# Group12_411_REV1.net
KiCad netlist of a schematic drawn in EAGLE
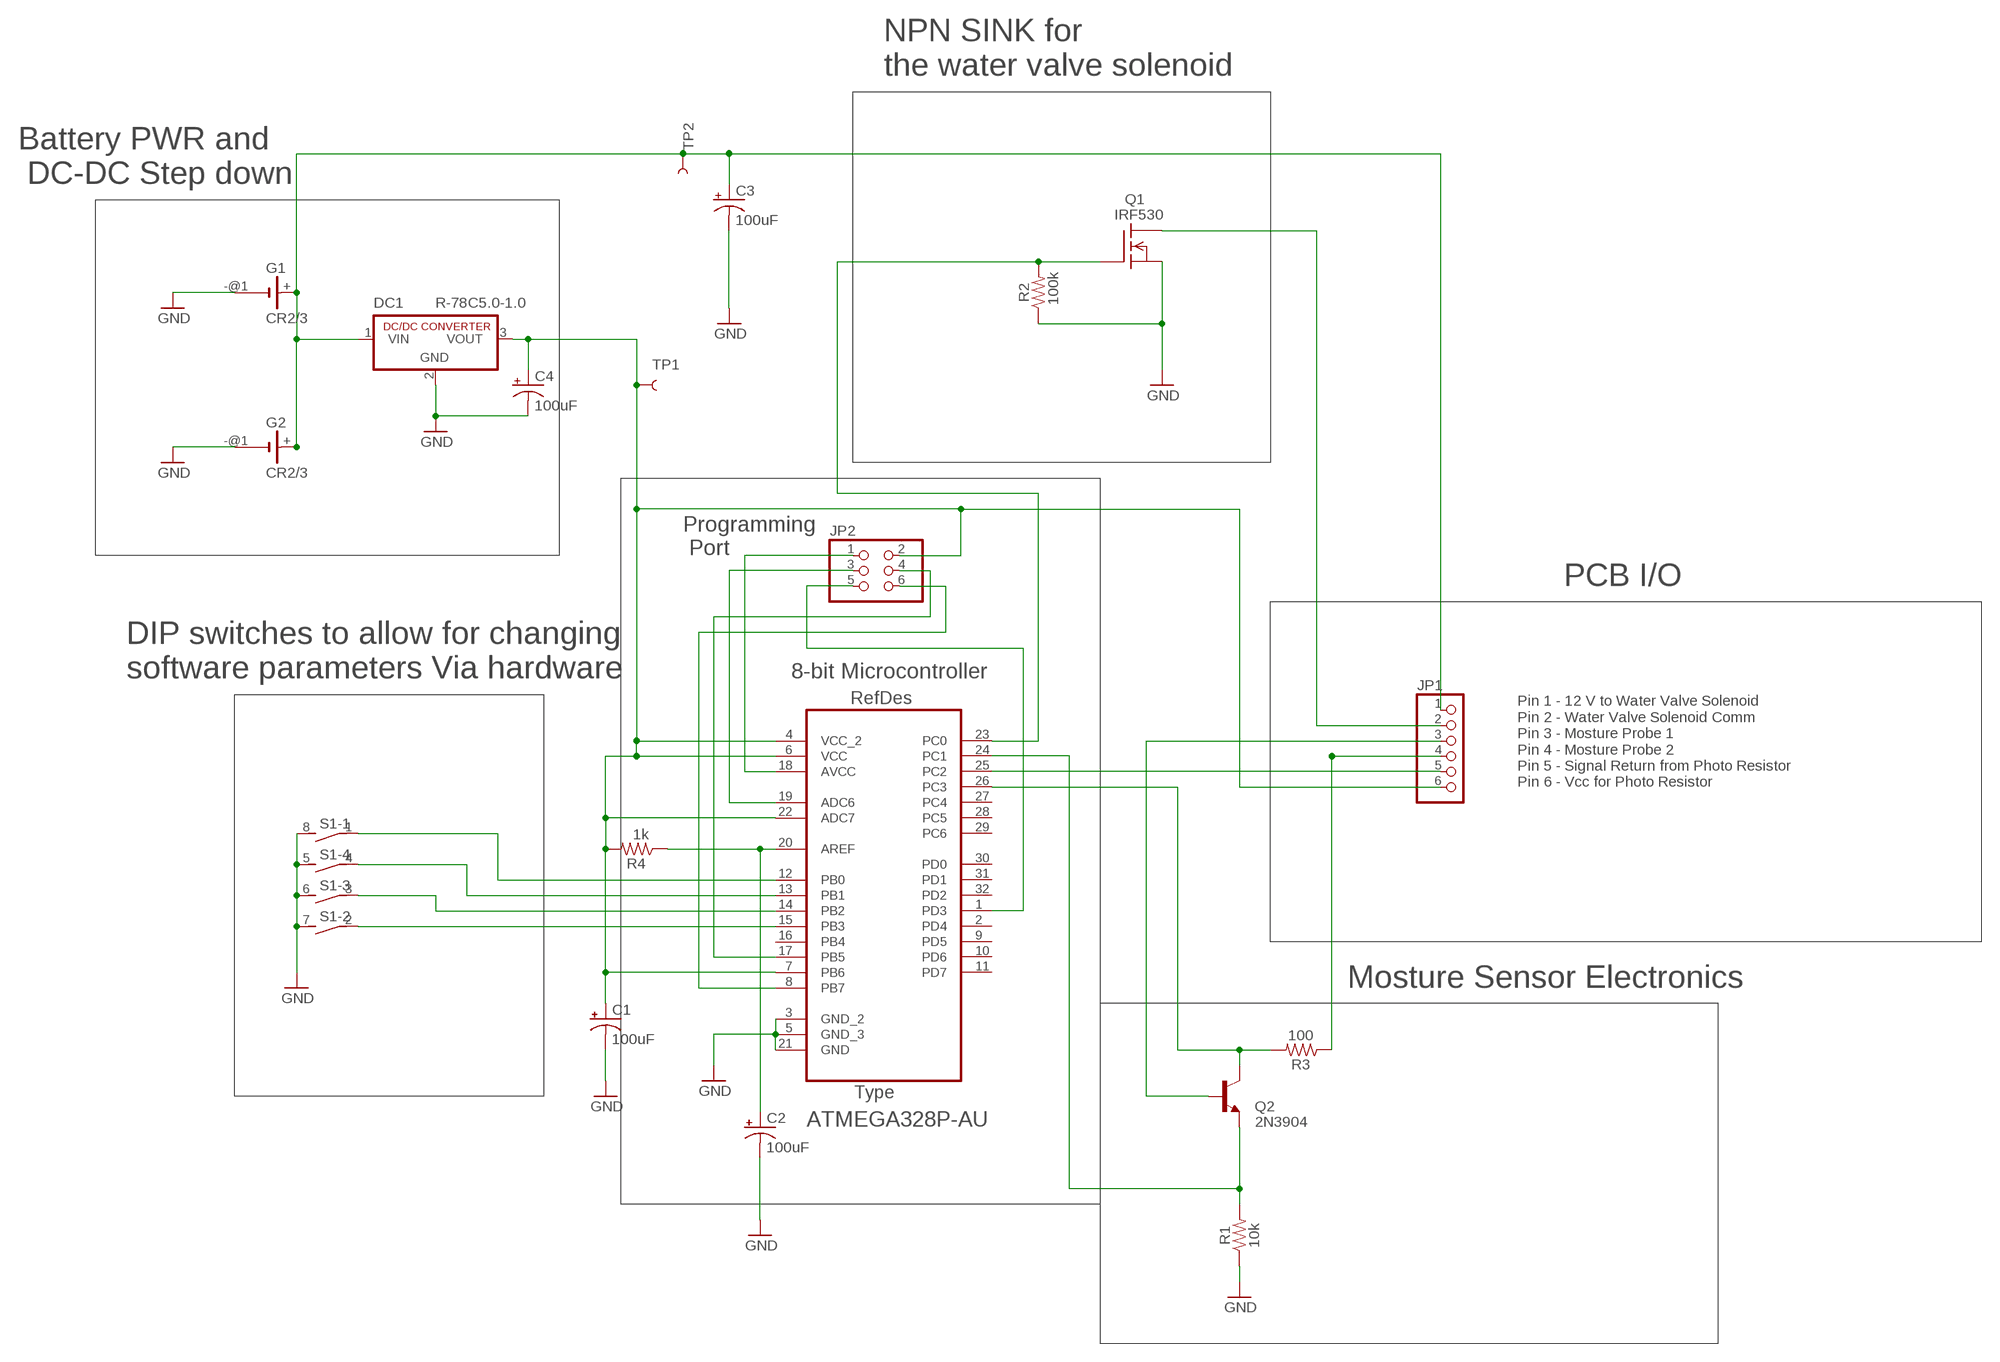
[diagram p0: schematic, sheet 1]

(export (version "E")
  (design (tool "Eeschema 10.0.6"))
  (components
    (comp (ref "ATMEGA328")
      (value "ATMEGA328P-AU")
      (footprint "eagle-import:QFP80P900X900X120-32N")
      (description "8-bit Microcontroller")
      (fields (field (name "MPN") "ATMEGA328P-AU"))
      (libsource (lib "eagle-import") (part "ATMEGA328P-AU"))
    )
    (comp (ref "C1")
      (value "100uF")
      (footprint "eagle-import:EIA7343")
      (libsource (lib "eagle-import") (part "100UF-POLAR-EIA7343-16V-10%(TANT)"))
    )
    (comp (ref "C2")
      (value "100uF")
      (footprint "eagle-import:EIA7343")
      (libsource (lib "eagle-import") (part "100UF-POLAR-EIA7343-16V-10%(TANT)"))
    )
    (comp (ref "C3")
      (value "100uF")
      (footprint "eagle-import:EIA7343")
      (libsource (lib "eagle-import") (part "100UF-POLAR-EIA7343-16V-10%(TANT)"))
    )
    (comp (ref "C4")
      (value "100uF")
      (footprint "eagle-import:EIA7343")
      (libsource (lib "eagle-import") (part "100UF-POLAR-EIA7343-16V-10%(TANT)"))
    )
    (comp (ref "DC1")
      (value "R-78C5.0-1.0")
      (footprint "eagle-import:SIP3")
      (libsource (lib "eagle-import") (part "R-78C-1.05.0"))
    )
    (comp (ref "G1")
      (value "CR2/3")
      (footprint "eagle-import:CR2_3")
      (libsource (lib "eagle-import") (part "CR2/3"))
    )
    (comp (ref "G2")
      (value "CR2/3")
      (footprint "eagle-import:CR2_3")
      (libsource (lib "eagle-import") (part "CR2/3"))
    )
    (comp (ref "JP1")
      (value "PINHD-1X6")
      (footprint "eagle-import:1X06")
      (libsource (lib "eagle-import") (part "PINHD-1X6"))
    )
    (comp (ref "JP2")
      (value "PINHD-2X3")
      (footprint "eagle-import:2X03")
      (libsource (lib "eagle-import") (part "PINHD-2X3"))
    )
    (comp (ref "Q1")
      (value "VN66AF")
      (footprint "eagle-import:TO202")
      (libsource (lib "eagle-import") (part "VN66AF"))
    )
    (comp (ref "Q2")
      (value "600mA/40V")
      (footprint "eagle-import:SOT23-3")
      (fields (field (name "Q") "2N3904"))
      (libsource (lib "eagle-import") (part "TRANS_NPN-MMBT2222AL"))
    )
    (comp (ref "R1")
      (value "R-US_M0805")
      (footprint "eagle-import:M0805")
      (fields (field (name "R") "10k"))
      (libsource (lib "eagle-import") (part "R-US_M0805"))
    )
    (comp (ref "R2")
      (value "R-US_M0805")
      (footprint "eagle-import:M0805")
      (fields (field (name "R") "100k"))
      (libsource (lib "eagle-import") (part "R-US_M0805"))
    )
    (comp (ref "R3")
      (value "R-US_M0805")
      (footprint "eagle-import:M0805")
      (fields (field (name "R") "100"))
      (libsource (lib "eagle-import") (part "R-US_M0805"))
    )
    (comp (ref "R4")
      (value "R-US_M0805")
      (footprint "eagle-import:M0805")
      (fields (field (name "R") "1k"))
      (libsource (lib "eagle-import") (part "R-US_M0805"))
    )
    (comp (ref "S1")
      (value "DIP04S")
      (footprint "eagle-import:DIP04S")
      (libsource (lib "eagle-import") (part "DIP04S"))
    )
    (comp (ref "TP1")
      (value "TEST-POINT3")
      (footprint "eagle-import:PAD.03X.03")
      (libsource (lib "eagle-import") (part "TEST-POINT3"))
    )
    (comp (ref "TP2")
      (value "TEST-POINT3")
      (footprint "eagle-import:PAD.03X.03")
      (libsource (lib "eagle-import") (part "TEST-POINT3"))
    )
  )
  (nets
    (net (code "1") (name "GND") (class "Default")
      (node (ref "ATMEGA328") (pin "21") (pinfunction "GND_21") (pintype "passive"))
      (node (ref "ATMEGA328") (pin "3") (pinfunction "GND_2_3") (pintype "passive"))
      (node (ref "ATMEGA328") (pin "5") (pinfunction "GND_3_5") (pintype "passive"))
      (node (ref "C1") (pin "C") (pinfunction "-_C") (pintype "passive"))
      (node (ref "C2") (pin "C") (pinfunction "-_C") (pintype "passive"))
      (node (ref "C3") (pin "C") (pinfunction "-_C") (pintype "passive"))
      (node (ref "C4") (pin "C") (pinfunction "-_C") (pintype "passive"))
      (node (ref "DC1") (pin "2") (pinfunction "GND_2") (pintype "passive"))
      (node (ref "G1") (pin "-@1") (pinfunction "-_-@1") (pintype "passive"))
      (node (ref "G2") (pin "-@1") (pinfunction "-_-@1") (pintype "passive"))
      (node (ref "Q1") (pin "1") (pinfunction "S_1") (pintype "passive"))
      (node (ref "R1") (pin "1") (pinfunction "1_1") (pintype "passive"))
      (node (ref "R2") (pin "1") (pinfunction "1_1") (pintype "passive"))
      (node (ref "S1") (pin "5") (pinfunction "2_5") (pintype "passive"))
      (node (ref "S1") (pin "6") (pinfunction "2_6") (pintype "passive"))
      (node (ref "S1") (pin "7") (pinfunction "2_7") (pintype "passive"))
      (node (ref "S1") (pin "8") (pinfunction "2_8") (pintype "passive"))
    )
    (net (code "2") (name "Net-(ATMEGA328-ADC6)") (class "Default")
      (node (ref "ATMEGA328") (pin "19") (pinfunction "ADC6_19") (pintype "input"))
      (node (ref "JP2") (pin "3") (pinfunction "3_3") (pintype "passive"))
    )
    (net (code "3") (name "Net-(ATMEGA328-ADC7)") (class "Default")
      (node (ref "ATMEGA328") (pin "22") (pinfunction "ADC7_22") (pintype "input"))
      (node (ref "ATMEGA328") (pin "4") (pinfunction "VCC_2_4") (pintype "power_in"))
      (node (ref "ATMEGA328") (pin "6") (pinfunction "VCC_6") (pintype "power_in"))
      (node (ref "ATMEGA328") (pin "7") (pinfunction "PB6_7") (pintype "bidirectional"))
      (node (ref "C1") (pin "A") (pinfunction "+_A") (pintype "passive"))
      (node (ref "C4") (pin "A") (pinfunction "+_A") (pintype "passive"))
      (node (ref "DC1") (pin "3") (pinfunction "VOUT_3") (pintype "passive"))
      (node (ref "JP1") (pin "6") (pinfunction "6_6") (pintype "passive"))
      (node (ref "JP2") (pin "2") (pinfunction "2_2") (pintype "passive"))
      (node (ref "R4") (pin "2") (pinfunction "2_2") (pintype "passive"))
      (node (ref "TP1") (pin "P$1") (pinfunction "1_P$1") (pintype "bidirectional"))
    )
    (net (code "4") (name "Net-(ATMEGA328-AREF)") (class "Default")
      (node (ref "ATMEGA328") (pin "20") (pinfunction "AREF_20") (pintype "input"))
      (node (ref "C2") (pin "A") (pinfunction "+_A") (pintype "passive"))
      (node (ref "R4") (pin "1") (pinfunction "1_1") (pintype "passive"))
    )
    (net (code "5") (name "Net-(ATMEGA328-AVCC)") (class "Default")
      (node (ref "ATMEGA328") (pin "18") (pinfunction "AVCC_18") (pintype "power_in"))
      (node (ref "JP2") (pin "1") (pinfunction "1_1") (pintype "passive"))
    )
    (net (code "6") (name "Net-(ATMEGA328-PB0)") (class "Default")
      (node (ref "ATMEGA328") (pin "12") (pinfunction "PB0_12") (pintype "bidirectional"))
      (node (ref "S1") (pin "1") (pinfunction "1_1") (pintype "passive"))
    )
    (net (code "7") (name "Net-(ATMEGA328-PB1)") (class "Default")
      (node (ref "ATMEGA328") (pin "13") (pinfunction "PB1_13") (pintype "bidirectional"))
      (node (ref "S1") (pin "4") (pinfunction "1_4") (pintype "passive"))
    )
    (net (code "8") (name "Net-(ATMEGA328-PB2)") (class "Default")
      (node (ref "ATMEGA328") (pin "14") (pinfunction "PB2_14") (pintype "bidirectional"))
      (node (ref "S1") (pin "3") (pinfunction "1_3") (pintype "passive"))
    )
    (net (code "9") (name "Net-(ATMEGA328-PB3)") (class "Default")
      (node (ref "ATMEGA328") (pin "15") (pinfunction "PB3_15") (pintype "bidirectional"))
      (node (ref "S1") (pin "2") (pinfunction "1_2") (pintype "passive"))
    )
    (net (code "10") (name "Net-(ATMEGA328-PB5)") (class "Default")
      (node (ref "ATMEGA328") (pin "17") (pinfunction "PB5_17") (pintype "bidirectional"))
      (node (ref "JP2") (pin "4") (pinfunction "4_4") (pintype "passive"))
    )
    (net (code "11") (name "Net-(ATMEGA328-PB7)") (class "Default")
      (node (ref "ATMEGA328") (pin "8") (pinfunction "PB7_8") (pintype "bidirectional"))
      (node (ref "JP2") (pin "6") (pinfunction "6_6") (pintype "passive"))
    )
    (net (code "12") (name "Net-(ATMEGA328-PC0)") (class "Default")
      (node (ref "ATMEGA328") (pin "23") (pinfunction "PC0_23") (pintype "bidirectional"))
      (node (ref "Q1") (pin "2") (pinfunction "G_2") (pintype "passive"))
      (node (ref "R2") (pin "2") (pinfunction "2_2") (pintype "passive"))
    )
    (net (code "13") (name "Net-(ATMEGA328-PC1)") (class "Default")
      (node (ref "ATMEGA328") (pin "24") (pinfunction "PC1_24") (pintype "bidirectional"))
      (node (ref "Q2") (pin "2") (pinfunction "E_2") (pintype "passive"))
      (node (ref "R1") (pin "2") (pinfunction "2_2") (pintype "passive"))
    )
    (net (code "14") (name "Net-(ATMEGA328-PC2)") (class "Default")
      (node (ref "ATMEGA328") (pin "25") (pinfunction "PC2_25") (pintype "bidirectional"))
      (node (ref "JP1") (pin "5") (pinfunction "5_5") (pintype "passive"))
    )
    (net (code "15") (name "Net-(ATMEGA328-PC3)") (class "Default")
      (node (ref "ATMEGA328") (pin "26") (pinfunction "PC3_26") (pintype "bidirectional"))
      (node (ref "Q2") (pin "3") (pinfunction "C_3") (pintype "passive"))
      (node (ref "R3") (pin "2") (pinfunction "2_2") (pintype "passive"))
    )
    (net (code "16") (name "Net-(ATMEGA328-PD3)") (class "Default")
      (node (ref "ATMEGA328") (pin "1") (pinfunction "PD3_1") (pintype "bidirectional"))
      (node (ref "JP2") (pin "5") (pinfunction "5_5") (pintype "passive"))
    )
    (net (code "17") (name "Net-(C3-+)") (class "Default")
      (node (ref "C3") (pin "A") (pinfunction "+_A") (pintype "passive"))
      (node (ref "DC1") (pin "1") (pinfunction "VIN_1") (pintype "passive"))
      (node (ref "G1") (pin "+") (pinfunction "+_+") (pintype "passive"))
      (node (ref "G2") (pin "+") (pinfunction "+_+") (pintype "passive"))
      (node (ref "JP1") (pin "1") (pinfunction "1_1") (pintype "passive"))
      (node (ref "TP2") (pin "P$1") (pinfunction "1_P$1") (pintype "bidirectional"))
    )
    (net (code "18") (name "Net-(JP1-Pad4)") (class "Default")
      (node (ref "JP1") (pin "4") (pinfunction "4_4") (pintype "passive"))
      (node (ref "R3") (pin "1") (pinfunction "1_1") (pintype "passive"))
    )
    (net (code "19") (name "Net-(Q1-D)") (class "Default")
      (node (ref "JP1") (pin "2") (pinfunction "2_2") (pintype "passive"))
      (node (ref "Q1") (pin "3") (pinfunction "D_3") (pintype "passive"))
    )
    (net (code "20") (name "Net-(Q2-B)") (class "Default")
      (node (ref "JP1") (pin "3") (pinfunction "3_3") (pintype "passive"))
      (node (ref "Q2") (pin "1") (pinfunction "B_1") (pintype "passive"))
    )
    (net (code "21") (name "unconnected-(ATMEGA328-PB4-Pad16)") (class "Default")
      (node (ref "ATMEGA328") (pin "16") (pinfunction "PB4_16") (pintype "bidirectional"))
    )
    (net (code "22") (name "unconnected-(ATMEGA328-PC4-Pad27)") (class "Default")
      (node (ref "ATMEGA328") (pin "27") (pinfunction "PC4_27") (pintype "bidirectional"))
    )
    (net (code "23") (name "unconnected-(ATMEGA328-PC5-Pad28)") (class "Default")
      (node (ref "ATMEGA328") (pin "28") (pinfunction "PC5_28") (pintype "bidirectional"))
    )
    (net (code "24") (name "unconnected-(ATMEGA328-PC6-Pad29)") (class "Default")
      (node (ref "ATMEGA328") (pin "29") (pinfunction "PC6_29") (pintype "bidirectional"))
    )
    (net (code "25") (name "unconnected-(ATMEGA328-PD0-Pad30)") (class "Default")
      (node (ref "ATMEGA328") (pin "30") (pinfunction "PD0_30") (pintype "bidirectional"))
    )
    (net (code "26") (name "unconnected-(ATMEGA328-PD1-Pad31)") (class "Default")
      (node (ref "ATMEGA328") (pin "31") (pinfunction "PD1_31") (pintype "bidirectional"))
    )
    (net (code "27") (name "unconnected-(ATMEGA328-PD2-Pad32)") (class "Default")
      (node (ref "ATMEGA328") (pin "32") (pinfunction "PD2_32") (pintype "bidirectional"))
    )
    (net (code "28") (name "unconnected-(ATMEGA328-PD4-Pad2)") (class "Default")
      (node (ref "ATMEGA328") (pin "2") (pinfunction "PD4_2") (pintype "bidirectional"))
    )
    (net (code "29") (name "unconnected-(ATMEGA328-PD5-Pad9)") (class "Default")
      (node (ref "ATMEGA328") (pin "9") (pinfunction "PD5_9") (pintype "bidirectional"))
    )
    (net (code "30") (name "unconnected-(ATMEGA328-PD6-Pad10)") (class "Default")
      (node (ref "ATMEGA328") (pin "10") (pinfunction "PD6_10") (pintype "bidirectional"))
    )
    (net (code "31") (name "unconnected-(ATMEGA328-PD7-Pad11)") (class "Default")
      (node (ref "ATMEGA328") (pin "11") (pinfunction "PD7_11") (pintype "bidirectional"))
    )
    (net (code "32") (name "unconnected-(G1---Pad-@2)") (class "Default")
      (node (ref "G1") (pin "-@2") (pinfunction "-_-@2") (pintype "passive"))
    )
    (net (code "33") (name "unconnected-(G2---Pad-@2)") (class "Default")
      (node (ref "G2") (pin "-@2") (pinfunction "-_-@2") (pintype "passive"))
    )
  )
)
